# tiny2313.net
KiCad netlist of a schematic drawn in EAGLE
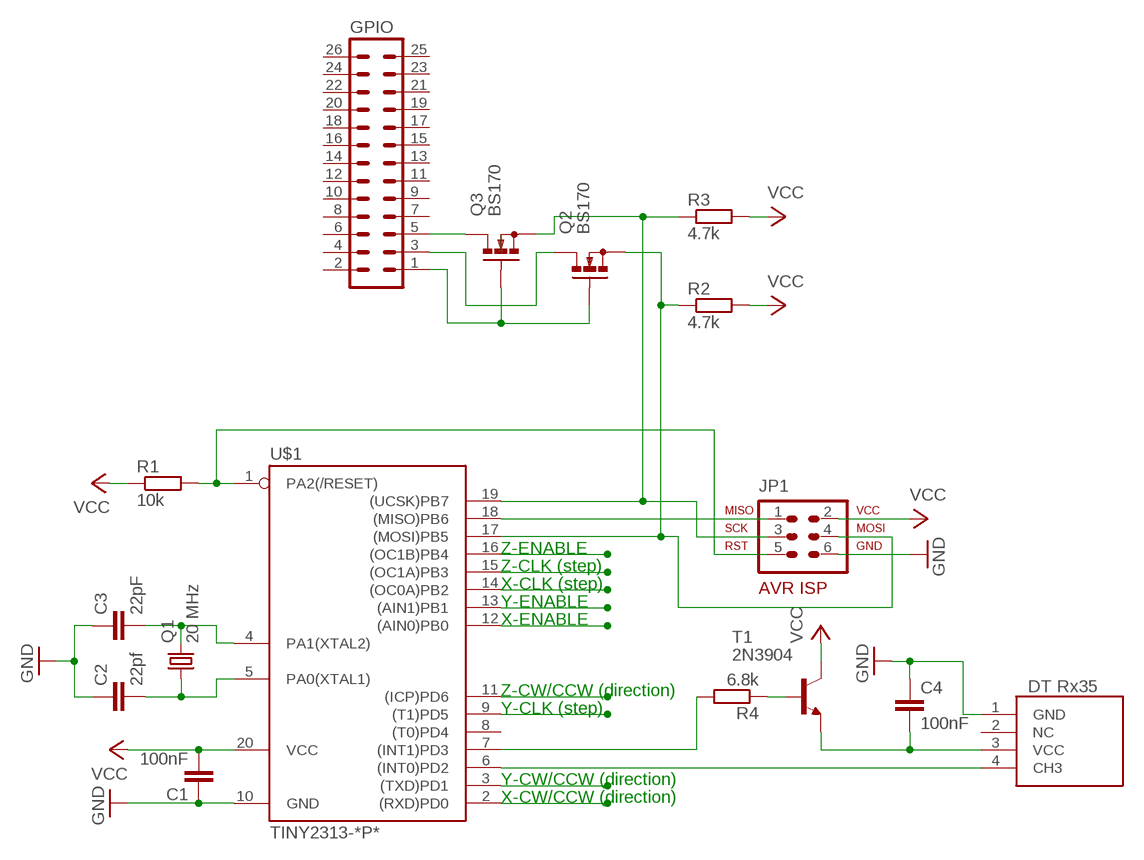
[diagram p0: schematic, sheet 1]

(export (version "E")
  (design (tool "Eeschema 10.0.6"))
  (components
    (comp (ref "C1")
      (value "100nF")
      (footprint "eagle-import:C2.5-2")
      (libsource (lib "eagle-import") (part "C2.5/2"))
    )
    (comp (ref "C2")
      (value "22pf")
      (footprint "eagle-import:C2.5-2")
      (libsource (lib "eagle-import") (part "C2.5/2"))
    )
    (comp (ref "C3")
      (value "22pF")
      (footprint "eagle-import:C2.5-2")
      (libsource (lib "eagle-import") (part "C2.5/2"))
    )
    (comp (ref "C4")
      (value "100nF")
      (footprint "eagle-import:C2.5-2")
      (libsource (lib "eagle-import") (part "C2.5/2"))
    )
    (comp (ref "GPIO")
      (value "ML26")
      (footprint "eagle-import:ML26")
      (libsource (lib "eagle-import") (part "ML26"))
    )
    (comp (ref "JP1")
      (value "AVR-ISP-6VERT")
      (footprint "eagle-import:AVR-ISP-6")
      (libsource (lib "eagle-import") (part "AVR-ISP-6VERT"))
    )
    (comp (ref "Q1")
      (value "20 MHz")
      (footprint "eagle-import:HC49_S")
      (libsource (lib "eagle-import") (part "CRYSTALHC49S"))
    )
    (comp (ref "Q2")
      (value "BS170")
      (footprint "eagle-import:SOT54E")
      (libsource (lib "eagle-import") (part "BS170"))
    )
    (comp (ref "Q3")
      (value "BS170")
      (footprint "eagle-import:SOT54E")
      (libsource (lib "eagle-import") (part "BS170"))
    )
    (comp (ref "R1")
      (value "10k")
      (footprint "eagle-import:0207_2V")
      (libsource (lib "eagle-import") (part "R-EU_0207/2V"))
    )
    (comp (ref "R2")
      (value "4.7k")
      (footprint "eagle-import:0207_2V")
      (libsource (lib "eagle-import") (part "R-EU_0207/2V"))
    )
    (comp (ref "R3")
      (value "4.7k")
      (footprint "eagle-import:0207_2V")
      (libsource (lib "eagle-import") (part "R-EU_0207/2V"))
    )
    (comp (ref "R4")
      (value "6.8k")
      (footprint "eagle-import:0207_12")
      (libsource (lib "eagle-import") (part "R-EU_0207/12"))
    )
    (comp (ref "T1")
      (value "2N3904")
      (footprint "eagle-import:TO92")
      (libsource (lib "eagle-import") (part "2N3904"))
    )
    (comp (ref "U$1")
      (value "TINY2313-*P*")
      (footprint "eagle-import:DIL20")
      (libsource (lib "eagle-import") (part "TINY2313-P"))
    )
    (comp (ref "U$2")
      (value "DTRX35")
      (footprint "eagle-import:DTRX35")
      (libsource (lib "eagle-import") (part "DTRX35"))
    )
  )
  (nets
    (net (code "1") (name "GND") (class "Default")
      (node (ref "C1") (pin "1") (pinfunction "1_1") (pintype "passive"))
      (node (ref "C2") (pin "1") (pinfunction "1_1") (pintype "passive"))
      (node (ref "C3") (pin "1") (pinfunction "1_1") (pintype "passive"))
      (node (ref "C4") (pin "1") (pinfunction "1_1") (pintype "passive"))
      (node (ref "JP1") (pin "6") (pinfunction "6_6") (pintype "passive"))
      (node (ref "U$1") (pin "10") (pinfunction "GND_10") (pintype "power_in"))
      (node (ref "U$2") (pin "1") (pinfunction "GND_1") (pintype "input"))
    )
    (net (code "2") (name "Net-(GPIO-Pad1)") (class "Default")
      (node (ref "GPIO") (pin "1") (pinfunction "1_1") (pintype "passive"))
      (node (ref "Q2") (pin "G") (pinfunction "G_G") (pintype "passive"))
      (node (ref "Q3") (pin "G") (pinfunction "G_G") (pintype "passive"))
    )
    (net (code "3") (name "Net-(GPIO-Pad3)") (class "Default")
      (node (ref "GPIO") (pin "3") (pinfunction "3_3") (pintype "passive"))
      (node (ref "Q2") (pin "D") (pinfunction "D_D") (pintype "passive"))
    )
    (net (code "4") (name "Net-(GPIO-Pad5)") (class "Default")
      (node (ref "GPIO") (pin "5") (pinfunction "5_5") (pintype "passive"))
      (node (ref "Q3") (pin "D") (pinfunction "D_D") (pintype "passive"))
    )
    (net (code "5") (name "Net-(T1-B)") (class "Default")
      (node (ref "R4") (pin "1") (pinfunction "1_1") (pintype "passive"))
      (node (ref "T1") (pin "2") (pinfunction "B_2") (pintype "passive"))
    )
    (net (code "6") (name "Net-(T1-E)") (class "Default")
      (node (ref "C4") (pin "2") (pinfunction "2_2") (pintype "passive"))
      (node (ref "T1") (pin "3") (pinfunction "E_3") (pintype "passive"))
      (node (ref "U$2") (pin "3") (pinfunction "VCC_3") (pintype "power_in"))
    )
    (net (code "7") (name "Net-(U$1-(INT0)PD2)") (class "Default")
      (node (ref "U$1") (pin "6") (pinfunction "(INT0)PD2_6") (pintype "bidirectional"))
      (node (ref "U$2") (pin "4") (pinfunction "CH3_4") (pintype "output"))
    )
    (net (code "8") (name "Net-(U$1-(INT1)PD3)") (class "Default")
      (node (ref "R4") (pin "2") (pinfunction "2_2") (pintype "passive"))
      (node (ref "U$1") (pin "7") (pinfunction "(INT1)PD3_7") (pintype "bidirectional"))
    )
    (net (code "9") (name "Net-(U$1-(MISO)PB6)") (class "Default")
      (node (ref "JP1") (pin "1") (pinfunction "1_1") (pintype "passive"))
      (node (ref "U$1") (pin "18") (pinfunction "(MISO)PB6_18") (pintype "bidirectional"))
    )
    (net (code "10") (name "Net-(U$1-(MOSI)PB5)") (class "Default")
      (node (ref "JP1") (pin "4") (pinfunction "4_4") (pintype "passive"))
      (node (ref "Q2") (pin "S") (pinfunction "S_S") (pintype "passive"))
      (node (ref "R2") (pin "1") (pinfunction "1_1") (pintype "passive"))
      (node (ref "U$1") (pin "17") (pinfunction "(MOSI)PB5_17") (pintype "bidirectional"))
    )
    (net (code "11") (name "Net-(U$1-(UCSK)PB7)") (class "Default")
      (node (ref "JP1") (pin "3") (pinfunction "3_3") (pintype "passive"))
      (node (ref "Q3") (pin "S") (pinfunction "S_S") (pintype "passive"))
      (node (ref "R3") (pin "1") (pinfunction "1_1") (pintype "passive"))
      (node (ref "U$1") (pin "19") (pinfunction "(UCSK)PB7_19") (pintype "bidirectional"))
    )
    (net (code "12") (name "Net-(U$1-PA0(XTAL1))") (class "Default")
      (node (ref "C2") (pin "2") (pinfunction "2_2") (pintype "passive"))
      (node (ref "Q1") (pin "1") (pinfunction "1_1") (pintype "passive"))
      (node (ref "U$1") (pin "5") (pinfunction "PA0(XTAL1)_5") (pintype "bidirectional"))
    )
    (net (code "13") (name "Net-(U$1-PA1(XTAL2))") (class "Default")
      (node (ref "C3") (pin "2") (pinfunction "2_2") (pintype "passive"))
      (node (ref "Q1") (pin "2") (pinfunction "2_2") (pintype "passive"))
      (node (ref "U$1") (pin "4") (pinfunction "PA1(XTAL2)_4") (pintype "bidirectional"))
    )
    (net (code "14") (name "Net-(U$1-PA2({slash}RESET))") (class "Default")
      (node (ref "JP1") (pin "5") (pinfunction "5_5") (pintype "passive"))
      (node (ref "R1") (pin "2") (pinfunction "2_2") (pintype "passive"))
      (node (ref "U$1") (pin "1") (pinfunction "PA2(/RESET)_1") (pintype "input"))
    )
    (net (code "15") (name "VCC") (class "Default")
      (node (ref "C1") (pin "2") (pinfunction "2_2") (pintype "passive"))
      (node (ref "JP1") (pin "2") (pinfunction "2_2") (pintype "passive"))
      (node (ref "R1") (pin "1") (pinfunction "1_1") (pintype "passive"))
      (node (ref "R2") (pin "2") (pinfunction "2_2") (pintype "passive"))
      (node (ref "R3") (pin "2") (pinfunction "2_2") (pintype "passive"))
      (node (ref "T1") (pin "1") (pinfunction "C_1") (pintype "passive"))
      (node (ref "U$1") (pin "20") (pinfunction "VCC_20") (pintype "power_in"))
    )
    (net (code "16") (name "unconnected-(GPIO-Pad2)") (class "Default")
      (node (ref "GPIO") (pin "2") (pinfunction "2_2") (pintype "passive"))
    )
    (net (code "17") (name "unconnected-(GPIO-Pad4)") (class "Default")
      (node (ref "GPIO") (pin "4") (pinfunction "4_4") (pintype "passive"))
    )
    (net (code "18") (name "unconnected-(GPIO-Pad6)") (class "Default")
      (node (ref "GPIO") (pin "6") (pinfunction "6_6") (pintype "passive"))
    )
    (net (code "19") (name "unconnected-(GPIO-Pad7)") (class "Default")
      (node (ref "GPIO") (pin "7") (pinfunction "7_7") (pintype "passive"))
    )
    (net (code "20") (name "unconnected-(GPIO-Pad8)") (class "Default")
      (node (ref "GPIO") (pin "8") (pinfunction "8_8") (pintype "passive"))
    )
    (net (code "21") (name "unconnected-(GPIO-Pad9)") (class "Default")
      (node (ref "GPIO") (pin "9") (pinfunction "9_9") (pintype "passive"))
    )
    (net (code "22") (name "unconnected-(GPIO-Pad10)") (class "Default")
      (node (ref "GPIO") (pin "10") (pinfunction "10_10") (pintype "passive"))
    )
    (net (code "23") (name "unconnected-(GPIO-Pad11)") (class "Default")
      (node (ref "GPIO") (pin "11") (pinfunction "11_11") (pintype "passive"))
    )
    (net (code "24") (name "unconnected-(GPIO-Pad12)") (class "Default")
      (node (ref "GPIO") (pin "12") (pinfunction "12_12") (pintype "passive"))
    )
    (net (code "25") (name "unconnected-(GPIO-Pad13)") (class "Default")
      (node (ref "GPIO") (pin "13") (pinfunction "13_13") (pintype "passive"))
    )
    (net (code "26") (name "unconnected-(GPIO-Pad14)") (class "Default")
      (node (ref "GPIO") (pin "14") (pinfunction "14_14") (pintype "passive"))
    )
    (net (code "27") (name "unconnected-(GPIO-Pad15)") (class "Default")
      (node (ref "GPIO") (pin "15") (pinfunction "15_15") (pintype "passive"))
    )
    (net (code "28") (name "unconnected-(GPIO-Pad16)") (class "Default")
      (node (ref "GPIO") (pin "16") (pinfunction "16_16") (pintype "passive"))
    )
    (net (code "29") (name "unconnected-(GPIO-Pad17)") (class "Default")
      (node (ref "GPIO") (pin "17") (pinfunction "17_17") (pintype "passive"))
    )
    (net (code "30") (name "unconnected-(GPIO-Pad18)") (class "Default")
      (node (ref "GPIO") (pin "18") (pinfunction "18_18") (pintype "passive"))
    )
    (net (code "31") (name "unconnected-(GPIO-Pad19)") (class "Default")
      (node (ref "GPIO") (pin "19") (pinfunction "19_19") (pintype "passive"))
    )
    (net (code "32") (name "unconnected-(GPIO-Pad20)") (class "Default")
      (node (ref "GPIO") (pin "20") (pinfunction "20_20") (pintype "passive"))
    )
    (net (code "33") (name "unconnected-(GPIO-Pad21)") (class "Default")
      (node (ref "GPIO") (pin "21") (pinfunction "21_21") (pintype "passive"))
    )
    (net (code "34") (name "unconnected-(GPIO-Pad22)") (class "Default")
      (node (ref "GPIO") (pin "22") (pinfunction "22_22") (pintype "passive"))
    )
    (net (code "35") (name "unconnected-(GPIO-Pad23)") (class "Default")
      (node (ref "GPIO") (pin "23") (pinfunction "23_23") (pintype "passive"))
    )
    (net (code "36") (name "unconnected-(GPIO-Pad24)") (class "Default")
      (node (ref "GPIO") (pin "24") (pinfunction "24_24") (pintype "passive"))
    )
    (net (code "37") (name "unconnected-(GPIO-Pad25)") (class "Default")
      (node (ref "GPIO") (pin "25") (pinfunction "25_25") (pintype "passive"))
    )
    (net (code "38") (name "unconnected-(GPIO-Pad26)") (class "Default")
      (node (ref "GPIO") (pin "26") (pinfunction "26_26") (pintype "passive"))
    )
    (net (code "39") (name "unconnected-(U$1-(AIN0)PB0-Pad12)") (class "Default")
      (node (ref "U$1") (pin "12") (pinfunction "(AIN0)PB0_12") (pintype "bidirectional"))
    )
    (net (code "40") (name "unconnected-(U$1-(AIN1)PB1-Pad13)") (class "Default")
      (node (ref "U$1") (pin "13") (pinfunction "(AIN1)PB1_13") (pintype "bidirectional"))
    )
    (net (code "41") (name "unconnected-(U$1-(ICP)PD6-Pad11)") (class "Default")
      (node (ref "U$1") (pin "11") (pinfunction "(ICP)PD6_11") (pintype "bidirectional"))
    )
    (net (code "42") (name "unconnected-(U$1-(OC0A)PB2-Pad14)") (class "Default")
      (node (ref "U$1") (pin "14") (pinfunction "(OC0A)PB2_14") (pintype "bidirectional"))
    )
    (net (code "43") (name "unconnected-(U$1-(OC1A)PB3-Pad15)") (class "Default")
      (node (ref "U$1") (pin "15") (pinfunction "(OC1A)PB3_15") (pintype "bidirectional"))
    )
    (net (code "44") (name "unconnected-(U$1-(OC1B)PB4-Pad16)") (class "Default")
      (node (ref "U$1") (pin "16") (pinfunction "(OC1B)PB4_16") (pintype "bidirectional"))
    )
    (net (code "45") (name "unconnected-(U$1-(RXD)PD0-Pad2)") (class "Default")
      (node (ref "U$1") (pin "2") (pinfunction "(RXD)PD0_2") (pintype "bidirectional"))
    )
    (net (code "46") (name "unconnected-(U$1-(T0)PD4-Pad8)") (class "Default")
      (node (ref "U$1") (pin "8") (pinfunction "(T0)PD4_8") (pintype "bidirectional"))
    )
    (net (code "47") (name "unconnected-(U$1-(T1)PD5-Pad9)") (class "Default")
      (node (ref "U$1") (pin "9") (pinfunction "(T1)PD5_9") (pintype "bidirectional"))
    )
    (net (code "48") (name "unconnected-(U$1-(TXD)PD1-Pad3)") (class "Default")
      (node (ref "U$1") (pin "3") (pinfunction "(TXD)PD1_3") (pintype "bidirectional"))
    )
    (net (code "49") (name "unconnected-(U$2-NC-Pad2)") (class "Default")
      (node (ref "U$2") (pin "2") (pinfunction "NC_2") (pintype "no_connect"))
    )
  )
)
